# Memory.net
KiCad netlist of a schematic drawn in Altium Designer
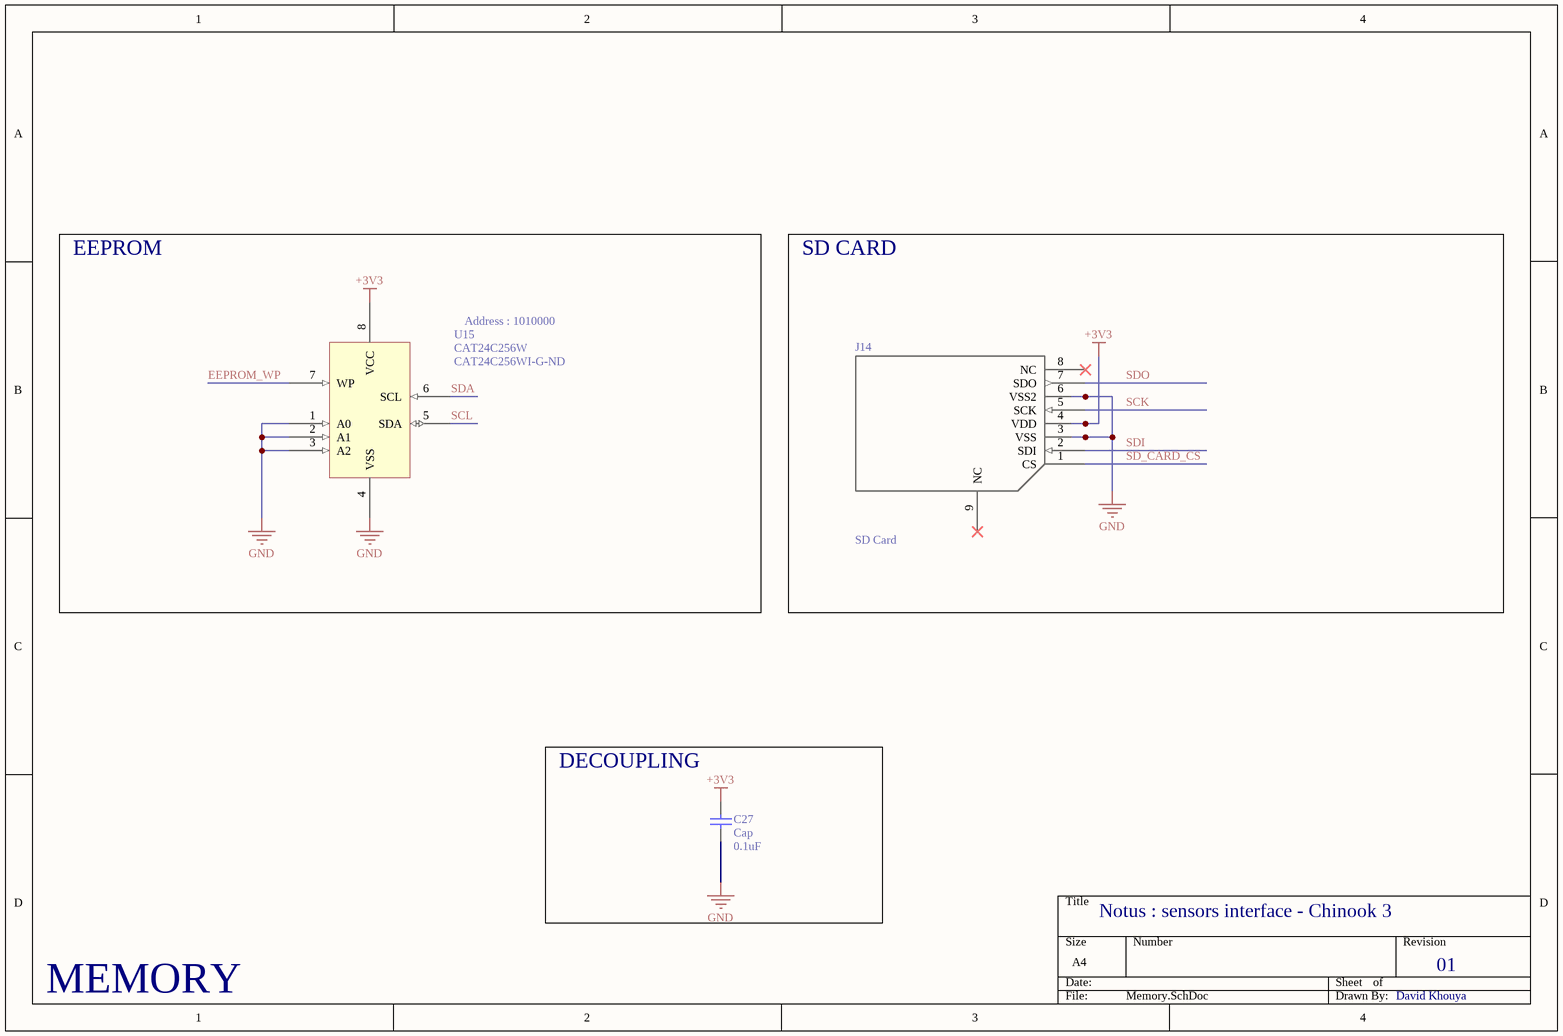
[diagram p0: Memory.SchDoc]

(export (version "E")
  (design (tool "Eeschema 10.0.6"))
  (components
    (comp (ref "C27")
      (value "Cap")
      (footprint "RESC2012N")
      (description "Capacitor")
      (fields (field (name "ALTIUM_VALUE") "0.1uF") (field (name "PUBLISHER") "Altium Limited"))
      (libsource (lib "Miscellaneous Devices") (part "Cap"))
    )
    (comp (ref "J14")
      (value "SD Card")
      (footprint "SD Card")
      (description "SPI Sd card connector pinout")
      (libsource (lib "dkhouya") (part "SD Card"))
    )
    (comp (ref "U15")
      (value "CAT24C256W")
      (footprint "8SOIC-2")
      (description "256 kb I2C CMOS Serial  EEPROM")
      (fields (field (name "SUPPLIER PART NUMBER 1") "CAT24C256WI-G-ND"))
      (libsource (lib "dkhouya") (part "CAT24C256W"))
    )
  )
  (nets
    (net (code "1") (name "+3V3") (class "Default")
      (node (ref "C27") (pin "2") (pinfunction "2_2") (pintype "passive"))
      (node (ref "J14") (pin "4") (pinfunction "VDD_4") (pintype "power_in"))
      (node (ref "U15") (pin "8") (pinfunction "VCC_8") (pintype "power_in"))
    )
    (net (code "2") (name "/EEPROM_WP") (class "Default")
      (node (ref "U15") (pin "7") (pinfunction "WP_7") (pintype "input"))
    )
    (net (code "3") (name "/SCK") (class "Default")
      (node (ref "J14") (pin "5") (pinfunction "SCK_5") (pintype "input"))
    )
    (net (code "4") (name "/SCL") (class "Default")
      (node (ref "U15") (pin "5") (pinfunction "SDA_5") (pintype "bidirectional"))
    )
    (net (code "5") (name "/SDA") (class "Default")
      (node (ref "U15") (pin "6") (pinfunction "SCL_6") (pintype "input"))
    )
    (net (code "6") (name "/SDI") (class "Default")
      (node (ref "J14") (pin "2") (pinfunction "SDI_2") (pintype "input"))
    )
    (net (code "7") (name "/SDO") (class "Default")
      (node (ref "J14") (pin "7") (pinfunction "SDO_7") (pintype "output"))
    )
    (net (code "8") (name "/SD_CARD_CS") (class "Default")
      (node (ref "J14") (pin "1") (pinfunction "CS_1") (pintype "passive"))
    )
    (net (code "9") (name "GND") (class "Default")
      (node (ref "C27") (pin "1") (pinfunction "1_1") (pintype "passive"))
      (node (ref "J14") (pin "3") (pinfunction "VSS_3") (pintype "power_in"))
      (node (ref "J14") (pin "6") (pinfunction "VSS2_6") (pintype "power_in"))
      (node (ref "U15") (pin "1") (pinfunction "A0_1") (pintype "input"))
      (node (ref "U15") (pin "2") (pinfunction "A1_2") (pintype "input"))
      (node (ref "U15") (pin "3") (pinfunction "A2_3") (pintype "input"))
      (node (ref "U15") (pin "4") (pinfunction "VSS_4") (pintype "passive"))
    )
    (net (code "10") (name "unconnected-(J14-NC-Pad8)") (class "Default")
      (node (ref "J14") (pin "8") (pinfunction "NC_8") (pintype "passive+no_connect"))
    )
    (net (code "11") (name "unconnected-(J14-NC-Pad9)") (class "Default")
      (node (ref "J14") (pin "9") (pinfunction "NC_9") (pintype "passive+no_connect"))
    )
  )
)
